# Ground_Station_2019-2020.net
KiCad netlist of a schematic drawn in EAGLE
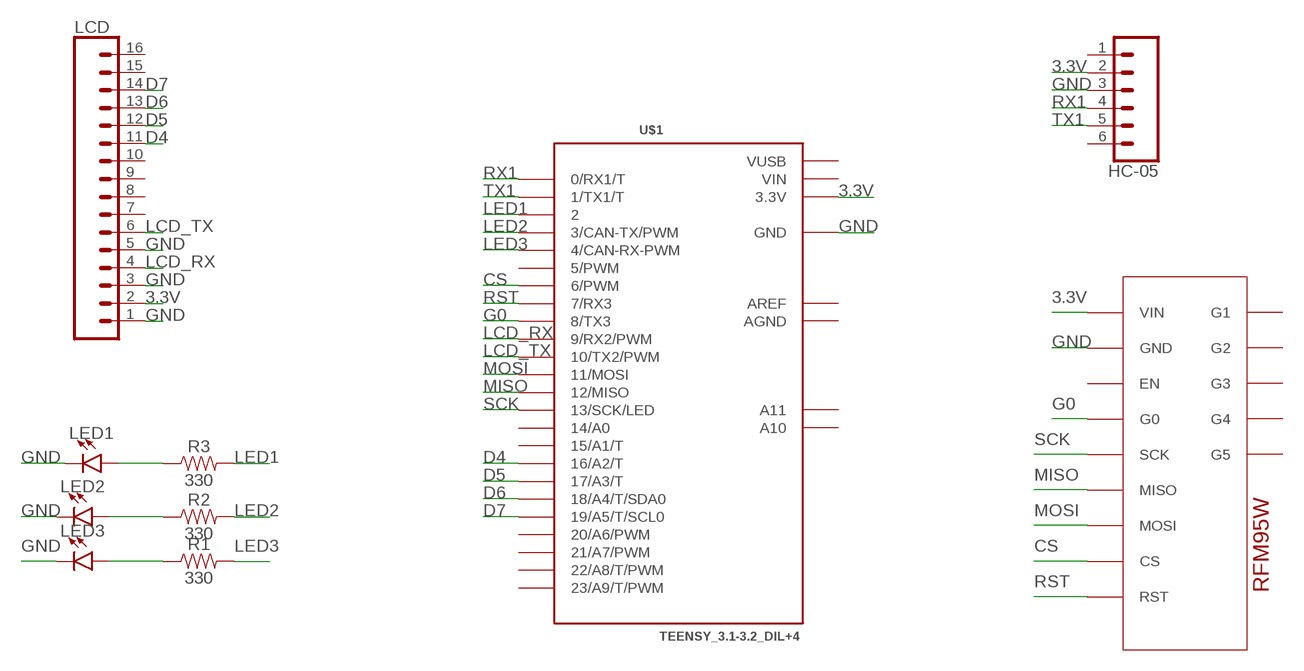
[diagram p0: schematic, sheet 1]

(export (version "E")
  (design (tool "Eeschema 10.0.6"))
  (components
    (comp (ref "HC-05")
      (value "CONN_06SILK_FEMALE_PTH")
      (footprint "eagle-import:1X06")
      (libsource (lib "eagle-import") (part "CONN_06SILK_FEMALE_PTH"))
    )
    (comp (ref "LCD")
      (value "CONN_16")
      (footprint "eagle-import:1X16")
      (libsource (lib "eagle-import") (part "CONN_16"))
    )
    (comp (ref "LED1")
      (value "LED5MM")
      (footprint "eagle-import:LED_5MM")
      (libsource (lib "eagle-import") (part "LED5MM"))
    )
    (comp (ref "LED2")
      (value "LED5MM")
      (footprint "eagle-import:LED_5MM")
      (libsource (lib "eagle-import") (part "LED5MM"))
    )
    (comp (ref "LED3")
      (value "LED5MM")
      (footprint "eagle-import:LED_5MM")
      (libsource (lib "eagle-import") (part "LED5MM"))
    )
    (comp (ref "R1")
      (value "330")
      (footprint "eagle-import:AXIAL-0.3")
      (libsource (lib "eagle-import") (part "330OHM-HORIZ-1/10W-5%"))
    )
    (comp (ref "R2")
      (value "330")
      (footprint "eagle-import:AXIAL-0.3")
      (libsource (lib "eagle-import") (part "330OHM-HORIZ-1/10W-5%"))
    )
    (comp (ref "R3")
      (value "330")
      (footprint "eagle-import:AXIAL-0.3")
      (libsource (lib "eagle-import") (part "330OHM-HORIZ-1/10W-5%"))
    )
    (comp (ref "U$1")
      (value "TEENSY_3.1-3.2_DIL+4")
      (footprint "eagle-import:TEENSY_3.0-3.2&LC_DIL+4")
      (libsource (lib "eagle-import") (part "TEENSY_3.1-3.2_DIL+4"))
    )
    (comp (ref "U1")
      (value "ADAFRUIT_RFM95W_LORA_RADIO")
      (footprint "eagle-import:ADAFRUIT_RFM95W_LORA_RADIO")
      (libsource (lib "eagle-import") (part "ADAFRUIT_RFM95W_LORA_RADIO"))
    )
  )
  (nets
    (net (code "1") (name "/3.3V") (class "Default")
      (node (ref "HC-05") (pin "2") (pinfunction "2_2") (pintype "passive"))
      (node (ref "LCD") (pin "2") (pinfunction "2_2") (pintype "passive"))
      (node (ref "U$1") (pin "3.3V") (pinfunction "3.3V_3.3V") (pintype "power_in"))
      (node (ref "U1") (pin "1") (pinfunction "VIN_1") (pintype "bidirectional"))
    )
    (net (code "2") (name "/AGND") (class "Default")
      (node (ref "U$1") (pin "AGND") (pinfunction "AGND_AGND") (pintype "power_in"))
    )
    (net (code "3") (name "/AREF") (class "Default")
      (node (ref "U$1") (pin "AREF") (pinfunction "AREF_AREF") (pintype "power_in"))
    )
    (net (code "4") (name "/CS") (class "Default")
      (node (ref "U$1") (pin "6") (pinfunction "6/PWM_6") (pintype "bidirectional"))
      (node (ref "U1") (pin "8") (pinfunction "CS_8") (pintype "bidirectional"))
    )
    (net (code "5") (name "/D4") (class "Default")
      (node (ref "LCD") (pin "11") (pinfunction "11_11") (pintype "passive"))
      (node (ref "U$1") (pin "16/A2") (pinfunction "16/A2/T_16/A2") (pintype "bidirectional"))
    )
    (net (code "6") (name "/D5") (class "Default")
      (node (ref "LCD") (pin "12") (pinfunction "12_12") (pintype "passive"))
      (node (ref "U$1") (pin "17/A3") (pinfunction "17/A3/T_17/A3") (pintype "bidirectional"))
    )
    (net (code "7") (name "/D6") (class "Default")
      (node (ref "LCD") (pin "13") (pinfunction "13_13") (pintype "passive"))
      (node (ref "U$1") (pin "18/A4") (pinfunction "18/A4/T/SDA0_18/A4") (pintype "bidirectional"))
    )
    (net (code "8") (name "/D7") (class "Default")
      (node (ref "LCD") (pin "14") (pinfunction "14_14") (pintype "passive"))
      (node (ref "U$1") (pin "19/A5") (pinfunction "19/A5/T/SCL0_19/A5") (pintype "bidirectional"))
    )
    (net (code "9") (name "/G0") (class "Default")
      (node (ref "U$1") (pin "8") (pinfunction "8/TX3_8") (pintype "bidirectional"))
      (node (ref "U1") (pin "4") (pinfunction "G0_4") (pintype "bidirectional"))
    )
    (net (code "10") (name "/GND") (class "Default")
      (node (ref "HC-05") (pin "3") (pinfunction "3_3") (pintype "passive"))
      (node (ref "LCD") (pin "1") (pinfunction "1_1") (pintype "passive"))
      (node (ref "LCD") (pin "3") (pinfunction "3_3") (pintype "passive"))
      (node (ref "LCD") (pin "5") (pinfunction "5_5") (pintype "passive"))
      (node (ref "LED1") (pin "K") (pinfunction "C_K") (pintype "passive"))
      (node (ref "LED2") (pin "K") (pinfunction "C_K") (pintype "passive"))
      (node (ref "LED3") (pin "K") (pinfunction "C_K") (pintype "passive"))
      (node (ref "U$1") (pin "GND") (pinfunction "GND_GND") (pintype "power_in"))
      (node (ref "U1") (pin "2") (pinfunction "GND_2") (pintype "bidirectional"))
    )
    (net (code "11") (name "/LCD_RX") (class "Default")
      (node (ref "LCD") (pin "4") (pinfunction "4_4") (pintype "passive"))
      (node (ref "U$1") (pin "9") (pinfunction "9/RX2/PWM_9") (pintype "bidirectional"))
    )
    (net (code "12") (name "/LCD_TX") (class "Default")
      (node (ref "LCD") (pin "6") (pinfunction "6_6") (pintype "passive"))
      (node (ref "U$1") (pin "10") (pinfunction "10/TX2/PWM_10") (pintype "bidirectional"))
    )
    (net (code "13") (name "/LED1") (class "Default")
      (node (ref "R3") (pin "P$2") (pinfunction "2_P$2") (pintype "passive"))
      (node (ref "U$1") (pin "2") (pinfunction "2_2") (pintype "bidirectional"))
    )
    (net (code "14") (name "/LED2") (class "Default")
      (node (ref "R2") (pin "P$2") (pinfunction "2_P$2") (pintype "passive"))
      (node (ref "U$1") (pin "3") (pinfunction "3/CAN-TX/PWM_3") (pintype "bidirectional"))
    )
    (net (code "15") (name "/LED3") (class "Default")
      (node (ref "R1") (pin "P$2") (pinfunction "2_P$2") (pintype "passive"))
      (node (ref "U$1") (pin "4") (pinfunction "4/CAN-RX-PWM_4") (pintype "bidirectional"))
    )
    (net (code "16") (name "/MISO") (class "Default")
      (node (ref "U$1") (pin "12") (pinfunction "12/MISO_12") (pintype "bidirectional"))
      (node (ref "U1") (pin "6") (pinfunction "MISO_6") (pintype "bidirectional"))
    )
    (net (code "17") (name "/MOSI") (class "Default")
      (node (ref "U$1") (pin "11") (pinfunction "11/MOSI_11") (pintype "bidirectional"))
      (node (ref "U1") (pin "7") (pinfunction "MOSI_7") (pintype "bidirectional"))
    )
    (net (code "18") (name "/RST") (class "Default")
      (node (ref "U$1") (pin "7") (pinfunction "7/RX3_7") (pintype "bidirectional"))
      (node (ref "U1") (pin "9") (pinfunction "RST_9") (pintype "bidirectional"))
    )
    (net (code "19") (name "/RX1") (class "Default")
      (node (ref "HC-05") (pin "4") (pinfunction "4_4") (pintype "passive"))
      (node (ref "U$1") (pin "0") (pinfunction "0/RX1/T_0") (pintype "bidirectional"))
    )
    (net (code "20") (name "/SCK") (class "Default")
      (node (ref "U$1") (pin "13") (pinfunction "13/SCK/LED_13") (pintype "bidirectional"))
      (node (ref "U1") (pin "5") (pinfunction "SCK_5") (pintype "bidirectional"))
    )
    (net (code "21") (name "/TX1") (class "Default")
      (node (ref "HC-05") (pin "5") (pinfunction "5_5") (pintype "passive"))
      (node (ref "U$1") (pin "1") (pinfunction "1/TX1/T_1") (pintype "bidirectional"))
    )
    (net (code "22") (name "/VIN") (class "Default")
      (node (ref "U$1") (pin "VIN") (pinfunction "VIN_VIN") (pintype "power_in"))
    )
    (net (code "23") (name "/VUSB") (class "Default")
      (node (ref "U$1") (pin "VUSB") (pinfunction "VUSB_VUSB") (pintype "power_in"))
    )
    (net (code "24") (name "Net-(R1-1)") (class "Default")
      (node (ref "LED3") (pin "A") (pinfunction "A_A") (pintype "passive"))
      (node (ref "R1") (pin "P$1") (pinfunction "1_P$1") (pintype "passive"))
    )
    (net (code "25") (name "Net-(R2-1)") (class "Default")
      (node (ref "LED2") (pin "A") (pinfunction "A_A") (pintype "passive"))
      (node (ref "R2") (pin "P$1") (pinfunction "1_P$1") (pintype "passive"))
    )
    (net (code "26") (name "Net-(R3-1)") (class "Default")
      (node (ref "LED1") (pin "A") (pinfunction "A_A") (pintype "passive"))
      (node (ref "R3") (pin "P$1") (pinfunction "1_P$1") (pintype "passive"))
    )
    (net (code "27") (name "unconnected-(HC-05-Pad1)") (class "Default")
      (node (ref "HC-05") (pin "1") (pinfunction "1_1") (pintype "passive"))
    )
    (net (code "28") (name "unconnected-(HC-05-Pad6)") (class "Default")
      (node (ref "HC-05") (pin "6") (pinfunction "6_6") (pintype "passive"))
    )
    (net (code "29") (name "unconnected-(LCD-Pad7)") (class "Default")
      (node (ref "LCD") (pin "7") (pinfunction "7_7") (pintype "passive"))
    )
    (net (code "30") (name "unconnected-(LCD-Pad8)") (class "Default")
      (node (ref "LCD") (pin "8") (pinfunction "8_8") (pintype "passive"))
    )
    (net (code "31") (name "unconnected-(LCD-Pad9)") (class "Default")
      (node (ref "LCD") (pin "9") (pinfunction "9_9") (pintype "passive"))
    )
    (net (code "32") (name "unconnected-(LCD-Pad10)") (class "Default")
      (node (ref "LCD") (pin "10") (pinfunction "10_10") (pintype "passive"))
    )
    (net (code "33") (name "unconnected-(LCD-Pad15)") (class "Default")
      (node (ref "LCD") (pin "15") (pinfunction "15_15") (pintype "passive"))
    )
    (net (code "34") (name "unconnected-(LCD-Pad16)") (class "Default")
      (node (ref "LCD") (pin "16") (pinfunction "16_16") (pintype "passive"))
    )
    (net (code "35") (name "unconnected-(U$1-5{slash}PWM-Pad5)") (class "Default")
      (node (ref "U$1") (pin "5") (pinfunction "5/PWM_5") (pintype "bidirectional"))
    )
    (net (code "36") (name "unconnected-(U$1-15{slash}A1{slash}T-Pad15{slash}A1)") (class "Default")
      (node (ref "U$1") (pin "15/A1") (pinfunction "15/A1/T_15/A1") (pintype "bidirectional"))
    )
    (net (code "37") (name "unconnected-(U$1-20{slash}A6{slash}PWM-Pad20{slash}A6)") (class "Default")
      (node (ref "U$1") (pin "20/A6") (pinfunction "20/A6/PWM_20/A6") (pintype "bidirectional"))
    )
    (net (code "38") (name "unconnected-(U$1-21{slash}A7{slash}PWM-Pad21{slash}A7)") (class "Default")
      (node (ref "U$1") (pin "21/A7") (pinfunction "21/A7/PWM_21/A7") (pintype "bidirectional"))
    )
    (net (code "39") (name "unconnected-(U$1-22{slash}A8{slash}T{slash}PWM-Pad22{slash}A8)") (class "Default")
      (node (ref "U$1") (pin "22/A8") (pinfunction "22/A8/T/PWM_22/A8") (pintype "bidirectional"))
    )
    (net (code "40") (name "unconnected-(U$1-23{slash}A9{slash}T{slash}PWM-Pad23{slash}A9)") (class "Default")
      (node (ref "U$1") (pin "23/A9") (pinfunction "23/A9/T/PWM_23/A9") (pintype "bidirectional"))
    )
    (net (code "41") (name "unconnected-(U$1-Pad14{slash}A0)") (class "Default")
      (node (ref "U$1") (pin "14/A0") (pinfunction "14/A0_14/A0") (pintype "bidirectional"))
    )
    (net (code "42") (name "unconnected-(U$1-PadA10)") (class "Default")
      (node (ref "U$1") (pin "A10") (pinfunction "A10_A10") (pintype "bidirectional"))
    )
    (net (code "43") (name "unconnected-(U$1-PadA11)") (class "Default")
      (node (ref "U$1") (pin "A11") (pinfunction "A11_A11") (pintype "bidirectional"))
    )
    (net (code "44") (name "unconnected-(U1-EN-Pad3)") (class "Default")
      (node (ref "U1") (pin "3") (pinfunction "EN_3") (pintype "bidirectional"))
    )
    (net (code "45") (name "unconnected-(U1-G1-Pad10)") (class "Default")
      (node (ref "U1") (pin "10") (pinfunction "G1_10") (pintype "bidirectional"))
    )
    (net (code "46") (name "unconnected-(U1-G2-Pad11)") (class "Default")
      (node (ref "U1") (pin "11") (pinfunction "G2_11") (pintype "bidirectional"))
    )
    (net (code "47") (name "unconnected-(U1-G3-Pad12)") (class "Default")
      (node (ref "U1") (pin "12") (pinfunction "G3_12") (pintype "bidirectional"))
    )
    (net (code "48") (name "unconnected-(U1-G4-Pad13)") (class "Default")
      (node (ref "U1") (pin "13") (pinfunction "G4_13") (pintype "bidirectional"))
    )
    (net (code "49") (name "unconnected-(U1-G5-Pad14)") (class "Default")
      (node (ref "U1") (pin "14") (pinfunction "G5_14") (pintype "bidirectional"))
    )
  )
)
